# wires.net
KiCad netlist of a schematic drawn in Altium Designer
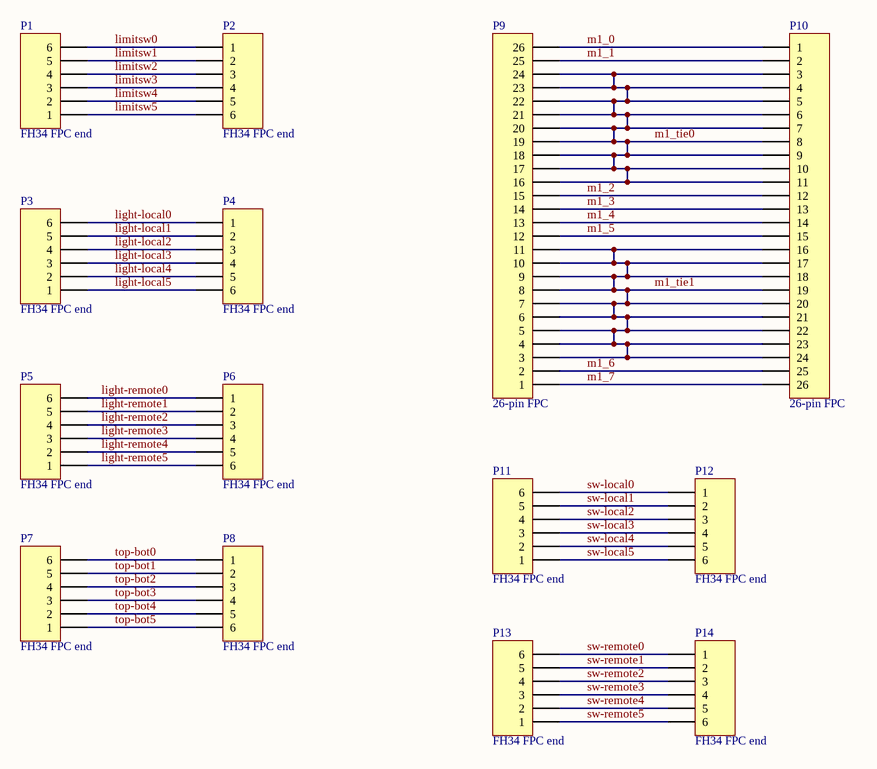
[diagram p0: wires.SchDoc]

(export (version "E")
  (design (tool "Eeschema 10.0.6"))
  (components
    (comp (ref "P1")
      (value "FH34 FPC end")
      (footprint "FPC-06-0.5MMP-0.3T-2.5MMS")
      (description "Header, 6-Pin")
      (fields (field (name "MPN") "FH34SRJ-6S-0.5SH(50)") (field (name "PUBLISHER") "Altium Limited"))
      (libsource (lib "Miscellaneous Connectors") (part "Header 6"))
    )
    (comp (ref "P2")
      (value "FH34 FPC end")
      (footprint "FPC-06-0.5MMP-0.3T-2.5MMS")
      (description "Header, 6-Pin")
      (fields (field (name "MPN") "FH34SRJ-6S-0.5SH(50)") (field (name "PUBLISHER") "Altium Limited"))
      (libsource (lib "") (part "Header 6_1"))
    )
    (comp (ref "P3")
      (value "FH34 FPC end")
      (footprint "FPC-06-0.5MMP-0.3T-2.5MMS")
      (description "Header, 6-Pin")
      (fields (field (name "MPN") "FH34SRJ-6S-0.5SH(50)") (field (name "PUBLISHER") "Altium Limited"))
      (libsource (lib "Miscellaneous Connectors") (part "Header 6"))
    )
    (comp (ref "P4")
      (value "FH34 FPC end")
      (footprint "FPC-06-0.5MMP-0.3T-2.5MMS")
      (description "Header, 6-Pin")
      (fields (field (name "MPN") "FH34SRJ-6S-0.5SH(50)") (field (name "PUBLISHER") "Altium Limited"))
      (libsource (lib "") (part "Header 6_1"))
    )
    (comp (ref "P5")
      (value "FH34 FPC end")
      (footprint "FPC-06-0.5MMP-0.3T-2.5MMS")
      (description "Header, 6-Pin")
      (fields (field (name "MPN") "FH34SRJ-6S-0.5SH(50)") (field (name "PUBLISHER") "Altium Limited"))
      (libsource (lib "Miscellaneous Connectors") (part "Header 6"))
    )
    (comp (ref "P6")
      (value "FH34 FPC end")
      (footprint "FPC-06-0.5MMP-0.3T-2.5MMS")
      (description "Header, 6-Pin")
      (fields (field (name "MPN") "FH34SRJ-6S-0.5SH(50)") (field (name "PUBLISHER") "Altium Limited"))
      (libsource (lib "") (part "Header 6_1"))
    )
    (comp (ref "P7")
      (value "FH34 FPC end")
      (footprint "FPC-06-0.5MMP-0.3T-2.5MMS")
      (description "Header, 6-Pin")
      (fields (field (name "MPN") "FH34SRJ-6S-0.5SH(50)") (field (name "PUBLISHER") "Altium Limited"))
      (libsource (lib "Miscellaneous Connectors") (part "Header 6"))
    )
    (comp (ref "P8")
      (value "FH34 FPC end")
      (footprint "FPC-06-0.5MMP-0.3T-2.5MMS")
      (description "Header, 6-Pin")
      (fields (field (name "MPN") "FH34SRJ-6S-0.5SH(50)") (field (name "PUBLISHER") "Altium Limited"))
      (libsource (lib "") (part "Header 6_1"))
    )
    (comp (ref "P9")
      (value "26-pin FPC")
      (footprint "FPC-26-0.5MMP-0.3T-2.5MMS")
      (description "26 Pin FPC header")
      (fields (field (name "MPN") "FH34SRJ-26S-0.5SH(99)"))
      (libsource (lib "commonsch-new") (part "FPC-26"))
    )
    (comp (ref "P10")
      (value "26-pin FPC")
      (footprint "FPC-26-0.5MMP-0.3T-2.5MMS")
      (description "26 Pin FPC header")
      (fields (field (name "MPN") "FH34SRJ-26S-0.5SH(99)"))
      (libsource (lib "") (part "FPC-26_1"))
    )
    (comp (ref "P11")
      (value "FH34 FPC end")
      (footprint "FPC-06-0.5MMP-0.3T-2.5MMS")
      (description "Header, 6-Pin")
      (fields (field (name "MPN") "FH34SRJ-6S-0.5SH(50)") (field (name "PUBLISHER") "Altium Limited"))
      (libsource (lib "Miscellaneous Connectors") (part "Header 6"))
    )
    (comp (ref "P12")
      (value "FH34 FPC end")
      (footprint "FPC-06-0.5MMP-0.3T-2.5MMS")
      (description "Header, 6-Pin")
      (fields (field (name "MPN") "FH34SRJ-6S-0.5SH(50)") (field (name "PUBLISHER") "Altium Limited"))
      (libsource (lib "") (part "Header 6_1"))
    )
    (comp (ref "P13")
      (value "FH34 FPC end")
      (footprint "FPC-06-0.5MMP-0.3T-2.5MMS")
      (description "Header, 6-Pin")
      (fields (field (name "MPN") "FH34SRJ-6S-0.5SH(50)") (field (name "PUBLISHER") "Altium Limited"))
      (libsource (lib "Miscellaneous Connectors") (part "Header 6"))
    )
    (comp (ref "P14")
      (value "FH34 FPC end")
      (footprint "FPC-06-0.5MMP-0.3T-2.5MMS")
      (description "Header, 6-Pin")
      (fields (field (name "MPN") "FH34SRJ-6S-0.5SH(50)") (field (name "PUBLISHER") "Altium Limited"))
      (libsource (lib "") (part "Header 6_1"))
    )
  )
  (nets
    (net (code "1") (name "/light-local0") (class "Default")
      (node (ref "P3") (pin "6") (pinfunction "6_6") (pintype "passive"))
      (node (ref "P4") (pin "1") (pinfunction "1_1") (pintype "passive"))
    )
    (net (code "2") (name "/light-local1") (class "Default")
      (node (ref "P3") (pin "5") (pinfunction "5_5") (pintype "passive"))
      (node (ref "P4") (pin "2") (pinfunction "2_2") (pintype "passive"))
    )
    (net (code "3") (name "/light-local2") (class "Default")
      (node (ref "P3") (pin "4") (pinfunction "4_4") (pintype "passive"))
      (node (ref "P4") (pin "3") (pinfunction "3_3") (pintype "passive"))
    )
    (net (code "4") (name "/light-local3") (class "Default")
      (node (ref "P3") (pin "3") (pinfunction "3_3") (pintype "passive"))
      (node (ref "P4") (pin "4") (pinfunction "4_4") (pintype "passive"))
    )
    (net (code "5") (name "/light-local4") (class "Default")
      (node (ref "P3") (pin "2") (pinfunction "2_2") (pintype "passive"))
      (node (ref "P4") (pin "5") (pinfunction "5_5") (pintype "passive"))
    )
    (net (code "6") (name "/light-local5") (class "Default")
      (node (ref "P3") (pin "1") (pinfunction "1_1") (pintype "passive"))
      (node (ref "P4") (pin "6") (pinfunction "6_6") (pintype "passive"))
    )
    (net (code "7") (name "/light-remote0") (class "Default")
      (node (ref "P5") (pin "6") (pinfunction "6_6") (pintype "passive"))
      (node (ref "P6") (pin "1") (pinfunction "1_1") (pintype "passive"))
    )
    (net (code "8") (name "/light-remote1") (class "Default")
      (node (ref "P5") (pin "5") (pinfunction "5_5") (pintype "passive"))
      (node (ref "P6") (pin "2") (pinfunction "2_2") (pintype "passive"))
    )
    (net (code "9") (name "/light-remote2") (class "Default")
      (node (ref "P5") (pin "4") (pinfunction "4_4") (pintype "passive"))
      (node (ref "P6") (pin "3") (pinfunction "3_3") (pintype "passive"))
    )
    (net (code "10") (name "/light-remote3") (class "Default")
      (node (ref "P5") (pin "3") (pinfunction "3_3") (pintype "passive"))
      (node (ref "P6") (pin "4") (pinfunction "4_4") (pintype "passive"))
    )
    (net (code "11") (name "/light-remote4") (class "Default")
      (node (ref "P5") (pin "2") (pinfunction "2_2") (pintype "passive"))
      (node (ref "P6") (pin "5") (pinfunction "5_5") (pintype "passive"))
    )
    (net (code "12") (name "/light-remote5") (class "Default")
      (node (ref "P5") (pin "1") (pinfunction "1_1") (pintype "passive"))
      (node (ref "P6") (pin "6") (pinfunction "6_6") (pintype "passive"))
    )
    (net (code "13") (name "/limitsw0") (class "Default")
      (node (ref "P1") (pin "6") (pinfunction "6_6") (pintype "passive"))
      (node (ref "P2") (pin "1") (pinfunction "1_1") (pintype "passive"))
    )
    (net (code "14") (name "/limitsw1") (class "Default")
      (node (ref "P1") (pin "5") (pinfunction "5_5") (pintype "passive"))
      (node (ref "P2") (pin "2") (pinfunction "2_2") (pintype "passive"))
    )
    (net (code "15") (name "/limitsw2") (class "Default")
      (node (ref "P1") (pin "4") (pinfunction "4_4") (pintype "passive"))
      (node (ref "P2") (pin "3") (pinfunction "3_3") (pintype "passive"))
    )
    (net (code "16") (name "/limitsw3") (class "Default")
      (node (ref "P1") (pin "3") (pinfunction "3_3") (pintype "passive"))
      (node (ref "P2") (pin "4") (pinfunction "4_4") (pintype "passive"))
    )
    (net (code "17") (name "/limitsw4") (class "Default")
      (node (ref "P1") (pin "2") (pinfunction "2_2") (pintype "passive"))
      (node (ref "P2") (pin "5") (pinfunction "5_5") (pintype "passive"))
    )
    (net (code "18") (name "/limitsw5") (class "Default")
      (node (ref "P1") (pin "1") (pinfunction "1_1") (pintype "passive"))
      (node (ref "P2") (pin "6") (pinfunction "6_6") (pintype "passive"))
    )
    (net (code "19") (name "/m1_0") (class "Default")
      (node (ref "P10") (pin "1") (pinfunction "1_1") (pintype "passive"))
      (node (ref "P9") (pin "26") (pinfunction "26_26") (pintype "passive"))
    )
    (net (code "20") (name "/m1_1") (class "Default")
      (node (ref "P10") (pin "2") (pinfunction "2_2") (pintype "passive"))
      (node (ref "P9") (pin "25") (pinfunction "25_25") (pintype "passive"))
    )
    (net (code "21") (name "/m1_2") (class "Default")
      (node (ref "P10") (pin "12") (pinfunction "12_12") (pintype "passive"))
      (node (ref "P9") (pin "15") (pinfunction "15_15") (pintype "passive"))
    )
    (net (code "22") (name "/m1_3") (class "Default")
      (node (ref "P10") (pin "13") (pinfunction "13_13") (pintype "passive"))
      (node (ref "P9") (pin "14") (pinfunction "14_14") (pintype "passive"))
    )
    (net (code "23") (name "/m1_4") (class "Default")
      (node (ref "P10") (pin "14") (pinfunction "14_14") (pintype "passive"))
      (node (ref "P9") (pin "13") (pinfunction "13_13") (pintype "passive"))
    )
    (net (code "24") (name "/m1_5") (class "Default")
      (node (ref "P10") (pin "15") (pinfunction "15_15") (pintype "passive"))
      (node (ref "P9") (pin "12") (pinfunction "12_12") (pintype "passive"))
    )
    (net (code "25") (name "/m1_6") (class "Default")
      (node (ref "P10") (pin "25") (pinfunction "25_25") (pintype "passive"))
      (node (ref "P9") (pin "2") (pinfunction "2_2") (pintype "passive"))
    )
    (net (code "26") (name "/m1_7") (class "Default")
      (node (ref "P10") (pin "26") (pinfunction "26_26") (pintype "passive"))
      (node (ref "P9") (pin "1") (pinfunction "1_1") (pintype "passive"))
    )
    (net (code "27") (name "/m1_tie0") (class "Default")
      (node (ref "P10") (pin "10") (pinfunction "10_10") (pintype "passive"))
      (node (ref "P10") (pin "11") (pinfunction "11_11") (pintype "passive"))
      (node (ref "P10") (pin "3") (pinfunction "3_3") (pintype "passive"))
      (node (ref "P10") (pin "4") (pinfunction "4_4") (pintype "passive"))
      (node (ref "P10") (pin "5") (pinfunction "5_5") (pintype "passive"))
      (node (ref "P10") (pin "6") (pinfunction "6_6") (pintype "passive"))
      (node (ref "P10") (pin "7") (pinfunction "7_7") (pintype "passive"))
      (node (ref "P10") (pin "8") (pinfunction "8_8") (pintype "passive"))
      (node (ref "P10") (pin "9") (pinfunction "9_9") (pintype "passive"))
      (node (ref "P9") (pin "16") (pinfunction "16_16") (pintype "passive"))
      (node (ref "P9") (pin "17") (pinfunction "17_17") (pintype "passive"))
      (node (ref "P9") (pin "18") (pinfunction "18_18") (pintype "passive"))
      (node (ref "P9") (pin "19") (pinfunction "19_19") (pintype "passive"))
      (node (ref "P9") (pin "20") (pinfunction "20_20") (pintype "passive"))
      (node (ref "P9") (pin "21") (pinfunction "21_21") (pintype "passive"))
      (node (ref "P9") (pin "22") (pinfunction "22_22") (pintype "passive"))
      (node (ref "P9") (pin "23") (pinfunction "23_23") (pintype "passive"))
      (node (ref "P9") (pin "24") (pinfunction "24_24") (pintype "passive"))
    )
    (net (code "28") (name "/m1_tie1") (class "Default")
      (node (ref "P10") (pin "16") (pinfunction "16_16") (pintype "passive"))
      (node (ref "P10") (pin "17") (pinfunction "17_17") (pintype "passive"))
      (node (ref "P10") (pin "18") (pinfunction "18_18") (pintype "passive"))
      (node (ref "P10") (pin "19") (pinfunction "19_19") (pintype "passive"))
      (node (ref "P10") (pin "20") (pinfunction "20_20") (pintype "passive"))
      (node (ref "P10") (pin "21") (pinfunction "21_21") (pintype "passive"))
      (node (ref "P10") (pin "22") (pinfunction "22_22") (pintype "passive"))
      (node (ref "P10") (pin "23") (pinfunction "23_23") (pintype "passive"))
      (node (ref "P10") (pin "24") (pinfunction "24_24") (pintype "passive"))
      (node (ref "P9") (pin "10") (pinfunction "10_10") (pintype "passive"))
      (node (ref "P9") (pin "11") (pinfunction "11_11") (pintype "passive"))
      (node (ref "P9") (pin "3") (pinfunction "3_3") (pintype "passive"))
      (node (ref "P9") (pin "4") (pinfunction "4_4") (pintype "passive"))
      (node (ref "P9") (pin "5") (pinfunction "5_5") (pintype "passive"))
      (node (ref "P9") (pin "6") (pinfunction "6_6") (pintype "passive"))
      (node (ref "P9") (pin "7") (pinfunction "7_7") (pintype "passive"))
      (node (ref "P9") (pin "8") (pinfunction "8_8") (pintype "passive"))
      (node (ref "P9") (pin "9") (pinfunction "9_9") (pintype "passive"))
    )
    (net (code "29") (name "/sw-local0") (class "Default")
      (node (ref "P11") (pin "6") (pinfunction "6_6") (pintype "passive"))
      (node (ref "P12") (pin "1") (pinfunction "1_1") (pintype "passive"))
    )
    (net (code "30") (name "/sw-local1") (class "Default")
      (node (ref "P11") (pin "5") (pinfunction "5_5") (pintype "passive"))
      (node (ref "P12") (pin "2") (pinfunction "2_2") (pintype "passive"))
    )
    (net (code "31") (name "/sw-local2") (class "Default")
      (node (ref "P11") (pin "4") (pinfunction "4_4") (pintype "passive"))
      (node (ref "P12") (pin "3") (pinfunction "3_3") (pintype "passive"))
    )
    (net (code "32") (name "/sw-local3") (class "Default")
      (node (ref "P11") (pin "3") (pinfunction "3_3") (pintype "passive"))
      (node (ref "P12") (pin "4") (pinfunction "4_4") (pintype "passive"))
    )
    (net (code "33") (name "/sw-local4") (class "Default")
      (node (ref "P11") (pin "2") (pinfunction "2_2") (pintype "passive"))
      (node (ref "P12") (pin "5") (pinfunction "5_5") (pintype "passive"))
    )
    (net (code "34") (name "/sw-local5") (class "Default")
      (node (ref "P11") (pin "1") (pinfunction "1_1") (pintype "passive"))
      (node (ref "P12") (pin "6") (pinfunction "6_6") (pintype "passive"))
    )
    (net (code "35") (name "/sw-remote0") (class "Default")
      (node (ref "P13") (pin "6") (pinfunction "6_6") (pintype "passive"))
      (node (ref "P14") (pin "1") (pinfunction "1_1") (pintype "passive"))
    )
    (net (code "36") (name "/sw-remote1") (class "Default")
      (node (ref "P13") (pin "5") (pinfunction "5_5") (pintype "passive"))
      (node (ref "P14") (pin "2") (pinfunction "2_2") (pintype "passive"))
    )
    (net (code "37") (name "/sw-remote2") (class "Default")
      (node (ref "P13") (pin "4") (pinfunction "4_4") (pintype "passive"))
      (node (ref "P14") (pin "3") (pinfunction "3_3") (pintype "passive"))
    )
    (net (code "38") (name "/sw-remote3") (class "Default")
      (node (ref "P13") (pin "3") (pinfunction "3_3") (pintype "passive"))
      (node (ref "P14") (pin "4") (pinfunction "4_4") (pintype "passive"))
    )
    (net (code "39") (name "/sw-remote4") (class "Default")
      (node (ref "P13") (pin "2") (pinfunction "2_2") (pintype "passive"))
      (node (ref "P14") (pin "5") (pinfunction "5_5") (pintype "passive"))
    )
    (net (code "40") (name "/sw-remote5") (class "Default")
      (node (ref "P13") (pin "1") (pinfunction "1_1") (pintype "passive"))
      (node (ref "P14") (pin "6") (pinfunction "6_6") (pintype "passive"))
    )
    (net (code "41") (name "/top-bot0") (class "Default")
      (node (ref "P7") (pin "6") (pinfunction "6_6") (pintype "passive"))
      (node (ref "P8") (pin "1") (pinfunction "1_1") (pintype "passive"))
    )
    (net (code "42") (name "/top-bot1") (class "Default")
      (node (ref "P7") (pin "5") (pinfunction "5_5") (pintype "passive"))
      (node (ref "P8") (pin "2") (pinfunction "2_2") (pintype "passive"))
    )
    (net (code "43") (name "/top-bot2") (class "Default")
      (node (ref "P7") (pin "4") (pinfunction "4_4") (pintype "passive"))
      (node (ref "P8") (pin "3") (pinfunction "3_3") (pintype "passive"))
    )
    (net (code "44") (name "/top-bot3") (class "Default")
      (node (ref "P7") (pin "3") (pinfunction "3_3") (pintype "passive"))
      (node (ref "P8") (pin "4") (pinfunction "4_4") (pintype "passive"))
    )
    (net (code "45") (name "/top-bot4") (class "Default")
      (node (ref "P7") (pin "2") (pinfunction "2_2") (pintype "passive"))
      (node (ref "P8") (pin "5") (pinfunction "5_5") (pintype "passive"))
    )
    (net (code "46") (name "/top-bot5") (class "Default")
      (node (ref "P7") (pin "1") (pinfunction "1_1") (pintype "passive"))
      (node (ref "P8") (pin "6") (pinfunction "6_6") (pintype "passive"))
    )
  )
)
